# GPS.net
KiCad netlist of a schematic drawn in EAGLE
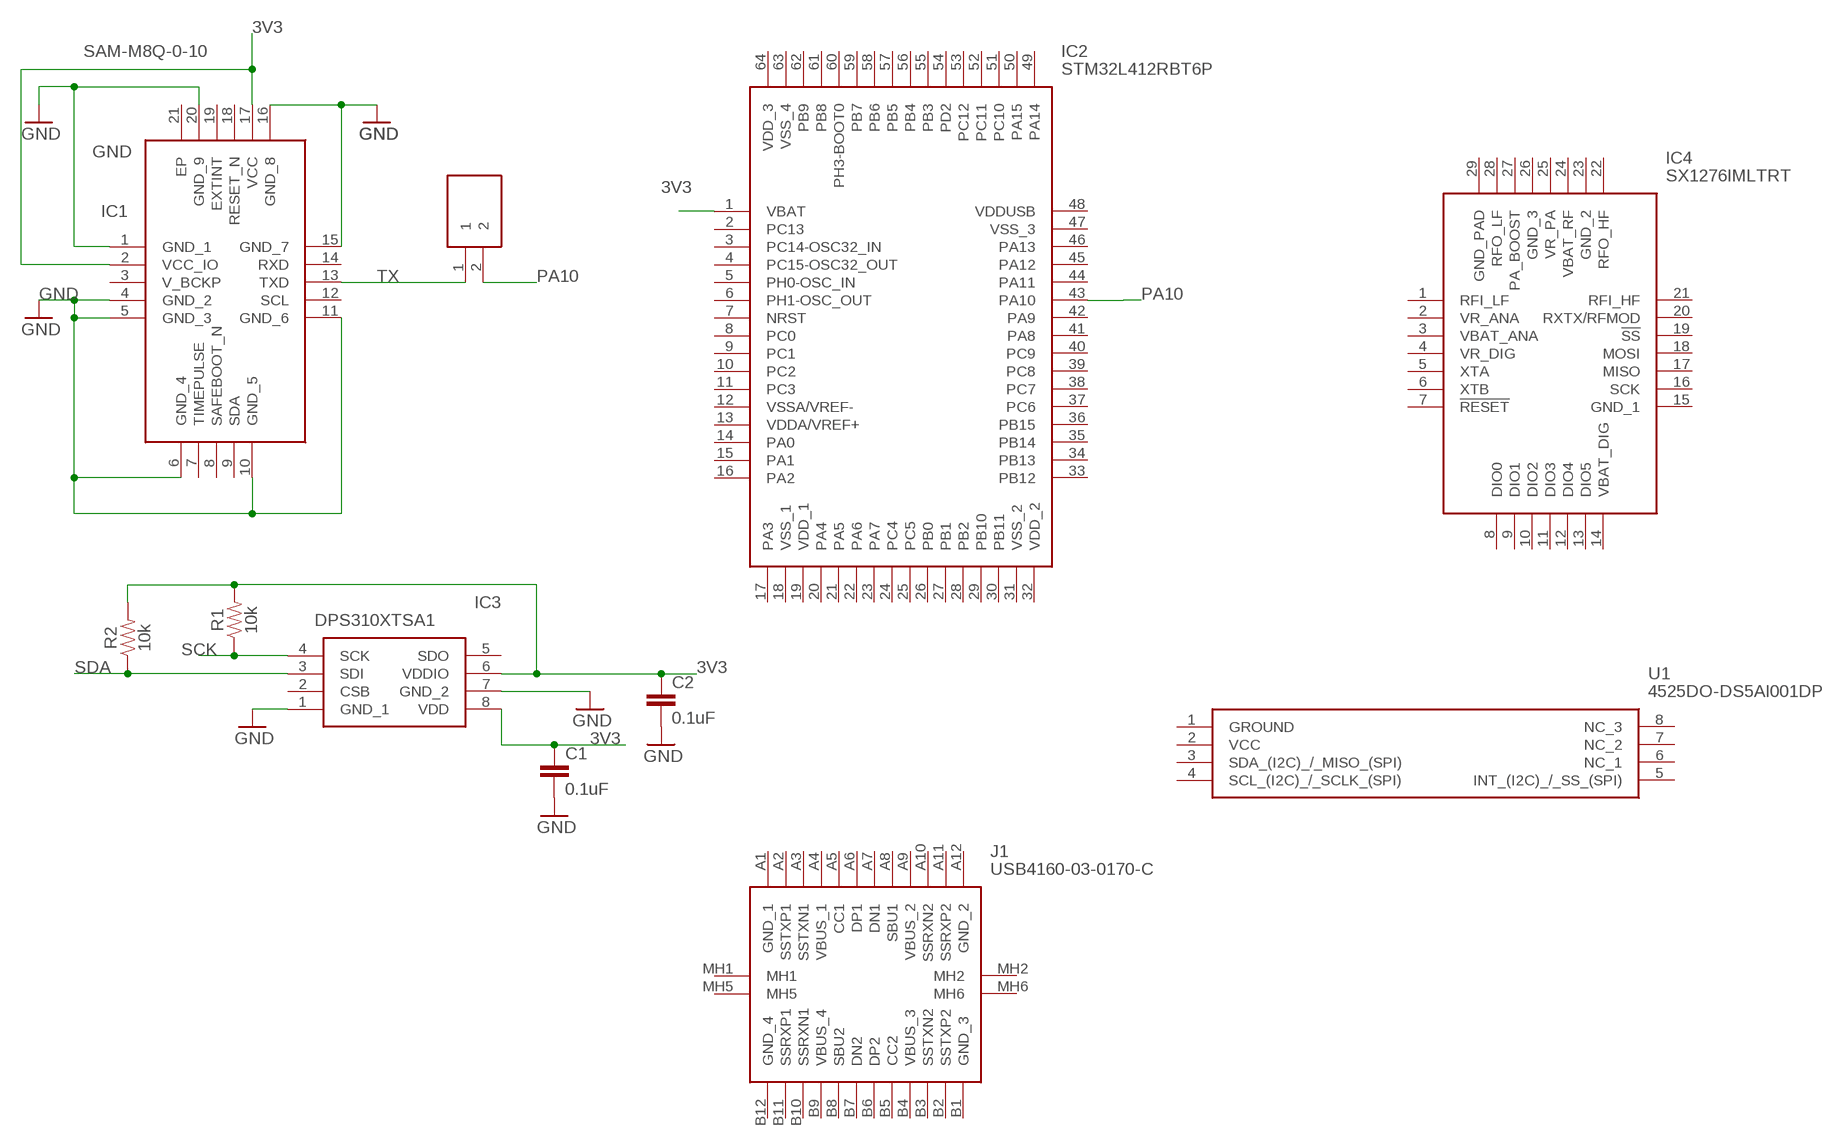
[diagram p0: schematic, sheet 1]

(export (version "E")
  (design (tool "Eeschema 10.0.6"))
  (components
    (comp (ref "C1")
      (value "0.1uF")
      (footprint "eagle-import:0402")
      (libsource (lib "eagle-import") (part "0.1UF-0402-6.3V-10%-X7R"))
    )
    (comp (ref "C2")
      (value "0.1uF")
      (footprint "eagle-import:0402")
      (libsource (lib "eagle-import") (part "0.1UF-0402-6.3V-10%-X7R"))
    )
    (comp (ref "FB1")
      (value "BLM15HD102SN1")
      (footprint "eagle-import:NFZ15SG152SN10B")
      (libsource (lib "eagle-import") (part "BLM15HD102SN1"))
    )
    (comp (ref "IC1")
      (value "SAM-M8Q-0-10")
      (footprint "eagle-import:SAMM8Q010")
      (libsource (lib "eagle-import") (part "SAM-M8Q-0-10"))
    )
    (comp (ref "IC2")
      (value "STM32L412RBT6P")
      (footprint "eagle-import:QFP50P1200X1200X160-64N")
      (fields (field (name "MOUSER_PART_NUMBER") "511-STM32L412RBT6P"))
      (libsource (lib "eagle-import") (part "STM32L412RBT6P"))
    )
    (comp (ref "IC3")
      (value "DPS310XTSA1")
      (footprint "eagle-import:DPS310XTSA1")
      (fields (field (name "MOUSER_PART_NUMBER") "726-DPS310XTSA1"))
      (libsource (lib "eagle-import") (part "DPS310XTSA1"))
    )
    (comp (ref "IC4")
      (value "SX1276IMLTRT")
      (footprint "eagle-import:QFN65P600X600X100-29N")
      (fields (field (name "MOUSER_PART_NUMBER") "947-SX1276IMLTRT"))
      (libsource (lib "eagle-import") (part "SX1276IMLTRT"))
    )
    (comp (ref "J1")
      (value "USB4160-03-0170-C")
      (footprint "eagle-import:USB4160030170C")
      (fields (field (name "MOUSER_PART_NUMBER") "640-USB4160-3-0170-C"))
      (libsource (lib "eagle-import") (part "USB4160-03-0170-C"))
    )
    (comp (ref "R1")
      (value "10k")
      (footprint "eagle-import:0402")
      (libsource (lib "eagle-import") (part "10KOHM-0402-1/16W-1%"))
    )
    (comp (ref "R2")
      (value "10k")
      (footprint "eagle-import:0402")
      (libsource (lib "eagle-import") (part "10KOHM-0402-1/16W-1%"))
    )
    (comp (ref "U1")
      (value "4525DO-DS5AI001DP")
      (footprint "eagle-import:4525DO-DS...P")
      (fields (field (name "MOUSER_PART_NUMBER") "824-4525DODS5AI001DP"))
      (libsource (lib "eagle-import") (part "4525DO-DS5AI001DP"))
    )
  )
  (nets
    (net (code "1") (name "/3V3") (class "Default")
      (node (ref "C1") (pin "1") (pinfunction "1_1") (pintype "passive"))
      (node (ref "C2") (pin "1") (pinfunction "1_1") (pintype "passive"))
      (node (ref "IC1") (pin "17") (pinfunction "VCC_17") (pintype "bidirectional"))
      (node (ref "IC1") (pin "2") (pinfunction "VCC_IO_2") (pintype "bidirectional"))
      (node (ref "IC2") (pin "1") (pinfunction "VBAT_1") (pintype "bidirectional"))
      (node (ref "IC3") (pin "6") (pinfunction "VDDIO_6") (pintype "bidirectional"))
      (node (ref "IC3") (pin "8") (pinfunction "VDD_8") (pintype "bidirectional"))
      (node (ref "R1") (pin "2") (pinfunction "2_2") (pintype "passive"))
      (node (ref "R2") (pin "2") (pinfunction "2_2") (pintype "passive"))
    )
    (net (code "2") (name "/GROUND") (class "Default")
      (node (ref "U1") (pin "1") (pinfunction "GROUND_1") (pintype "power_in"))
    )
    (net (code "3") (name "/PA10") (class "Default")
      (node (ref "FB1") (pin "2") (pinfunction "2_2") (pintype "bidirectional"))
      (node (ref "IC2") (pin "43") (pinfunction "PA10_43") (pintype "bidirectional"))
    )
    (net (code "4") (name "/SCK") (class "Default")
      (node (ref "IC3") (pin "4") (pinfunction "SCK_4") (pintype "bidirectional"))
      (node (ref "R1") (pin "1") (pinfunction "1_1") (pintype "passive"))
    )
    (net (code "5") (name "/SDA") (class "Default")
      (node (ref "IC3") (pin "3") (pinfunction "SDI_3") (pintype "bidirectional"))
      (node (ref "R2") (pin "1") (pinfunction "1_1") (pintype "passive"))
    )
    (net (code "6") (name "/TX") (class "Default")
      (node (ref "FB1") (pin "1") (pinfunction "1_1") (pintype "bidirectional"))
      (node (ref "IC1") (pin "13") (pinfunction "TXD_13") (pintype "bidirectional"))
    )
    (net (code "7") (name "/VCC") (class "Default")
      (node (ref "U1") (pin "2") (pinfunction "VCC_2") (pintype "power_in"))
    )
    (net (code "8") (name "GND") (class "Default")
      (node (ref "C1") (pin "2") (pinfunction "2_2") (pintype "passive"))
      (node (ref "C2") (pin "2") (pinfunction "2_2") (pintype "passive"))
      (node (ref "IC1") (pin "1") (pinfunction "GND_1_1") (pintype "bidirectional"))
      (node (ref "IC1") (pin "10") (pinfunction "GND_5_10") (pintype "bidirectional"))
      (node (ref "IC1") (pin "11") (pinfunction "GND_6_11") (pintype "bidirectional"))
      (node (ref "IC1") (pin "15") (pinfunction "GND_7_15") (pintype "bidirectional"))
      (node (ref "IC1") (pin "16") (pinfunction "GND_8_16") (pintype "bidirectional"))
      (node (ref "IC1") (pin "20") (pinfunction "GND_9_20") (pintype "bidirectional"))
      (node (ref "IC1") (pin "4") (pinfunction "GND_2_4") (pintype "bidirectional"))
      (node (ref "IC1") (pin "5") (pinfunction "GND_3_5") (pintype "bidirectional"))
      (node (ref "IC1") (pin "6") (pinfunction "GND_4_6") (pintype "bidirectional"))
      (node (ref "IC3") (pin "1") (pinfunction "GND_1_1") (pintype "bidirectional"))
      (node (ref "IC3") (pin "7") (pinfunction "GND_2_7") (pintype "bidirectional"))
    )
    (net (code "9") (name "unconnected-(IC1-EP-Pad21)") (class "Default")
      (node (ref "IC1") (pin "21") (pinfunction "EP_21") (pintype "bidirectional"))
    )
    (net (code "10") (name "unconnected-(IC1-EXTINT-Pad19)") (class "Default")
      (node (ref "IC1") (pin "19") (pinfunction "EXTINT_19") (pintype "bidirectional"))
    )
    (net (code "11") (name "unconnected-(IC1-RESET_N-Pad18)") (class "Default")
      (node (ref "IC1") (pin "18") (pinfunction "RESET_N_18") (pintype "bidirectional"))
    )
    (net (code "12") (name "unconnected-(IC1-RXD-Pad14)") (class "Default")
      (node (ref "IC1") (pin "14") (pinfunction "RXD_14") (pintype "bidirectional"))
    )
    (net (code "13") (name "unconnected-(IC1-SAFEBOOT_N-Pad8)") (class "Default")
      (node (ref "IC1") (pin "8") (pinfunction "SAFEBOOT_N_8") (pintype "bidirectional"))
    )
    (net (code "14") (name "unconnected-(IC1-SCL-Pad12)") (class "Default")
      (node (ref "IC1") (pin "12") (pinfunction "SCL_12") (pintype "bidirectional"))
    )
    (net (code "15") (name "unconnected-(IC1-SDA-Pad9)") (class "Default")
      (node (ref "IC1") (pin "9") (pinfunction "SDA_9") (pintype "bidirectional"))
    )
    (net (code "16") (name "unconnected-(IC1-TIMEPULSE-Pad7)") (class "Default")
      (node (ref "IC1") (pin "7") (pinfunction "TIMEPULSE_7") (pintype "bidirectional"))
    )
    (net (code "17") (name "unconnected-(IC1-V_BCKP-Pad3)") (class "Default")
      (node (ref "IC1") (pin "3") (pinfunction "V_BCKP_3") (pintype "bidirectional"))
    )
    (net (code "18") (name "unconnected-(IC2-NRST-Pad7)") (class "Default")
      (node (ref "IC2") (pin "7") (pinfunction "NRST_7") (pintype "bidirectional"))
    )
    (net (code "19") (name "unconnected-(IC2-PA0-Pad14)") (class "Default")
      (node (ref "IC2") (pin "14") (pinfunction "PA0_14") (pintype "bidirectional"))
    )
    (net (code "20") (name "unconnected-(IC2-PA1-Pad15)") (class "Default")
      (node (ref "IC2") (pin "15") (pinfunction "PA1_15") (pintype "bidirectional"))
    )
    (net (code "21") (name "unconnected-(IC2-PA2-Pad16)") (class "Default")
      (node (ref "IC2") (pin "16") (pinfunction "PA2_16") (pintype "bidirectional"))
    )
    (net (code "22") (name "unconnected-(IC2-PA3-Pad17)") (class "Default")
      (node (ref "IC2") (pin "17") (pinfunction "PA3_17") (pintype "bidirectional"))
    )
    (net (code "23") (name "unconnected-(IC2-PA4-Pad20)") (class "Default")
      (node (ref "IC2") (pin "20") (pinfunction "PA4_20") (pintype "bidirectional"))
    )
    (net (code "24") (name "unconnected-(IC2-PA5-Pad21)") (class "Default")
      (node (ref "IC2") (pin "21") (pinfunction "PA5_21") (pintype "bidirectional"))
    )
    (net (code "25") (name "unconnected-(IC2-PA6-Pad22)") (class "Default")
      (node (ref "IC2") (pin "22") (pinfunction "PA6_22") (pintype "bidirectional"))
    )
    (net (code "26") (name "unconnected-(IC2-PA7-Pad23)") (class "Default")
      (node (ref "IC2") (pin "23") (pinfunction "PA7_23") (pintype "bidirectional"))
    )
    (net (code "27") (name "unconnected-(IC2-PA8-Pad41)") (class "Default")
      (node (ref "IC2") (pin "41") (pinfunction "PA8_41") (pintype "bidirectional"))
    )
    (net (code "28") (name "unconnected-(IC2-PA9-Pad42)") (class "Default")
      (node (ref "IC2") (pin "42") (pinfunction "PA9_42") (pintype "bidirectional"))
    )
    (net (code "29") (name "unconnected-(IC2-PA11-Pad44)") (class "Default")
      (node (ref "IC2") (pin "44") (pinfunction "PA11_44") (pintype "bidirectional"))
    )
    (net (code "30") (name "unconnected-(IC2-PA12-Pad45)") (class "Default")
      (node (ref "IC2") (pin "45") (pinfunction "PA12_45") (pintype "bidirectional"))
    )
    (net (code "31") (name "unconnected-(IC2-PA13-Pad46)") (class "Default")
      (node (ref "IC2") (pin "46") (pinfunction "PA13_46") (pintype "bidirectional"))
    )
    (net (code "32") (name "unconnected-(IC2-PA14-Pad49)") (class "Default")
      (node (ref "IC2") (pin "49") (pinfunction "PA14_49") (pintype "bidirectional"))
    )
    (net (code "33") (name "unconnected-(IC2-PA15-Pad50)") (class "Default")
      (node (ref "IC2") (pin "50") (pinfunction "PA15_50") (pintype "bidirectional"))
    )
    (net (code "34") (name "unconnected-(IC2-PB0-Pad26)") (class "Default")
      (node (ref "IC2") (pin "26") (pinfunction "PB0_26") (pintype "bidirectional"))
    )
    (net (code "35") (name "unconnected-(IC2-PB1-Pad27)") (class "Default")
      (node (ref "IC2") (pin "27") (pinfunction "PB1_27") (pintype "bidirectional"))
    )
    (net (code "36") (name "unconnected-(IC2-PB2-Pad28)") (class "Default")
      (node (ref "IC2") (pin "28") (pinfunction "PB2_28") (pintype "bidirectional"))
    )
    (net (code "37") (name "unconnected-(IC2-PB3-Pad55)") (class "Default")
      (node (ref "IC2") (pin "55") (pinfunction "PB3_55") (pintype "bidirectional"))
    )
    (net (code "38") (name "unconnected-(IC2-PB4-Pad56)") (class "Default")
      (node (ref "IC2") (pin "56") (pinfunction "PB4_56") (pintype "bidirectional"))
    )
    (net (code "39") (name "unconnected-(IC2-PB5-Pad57)") (class "Default")
      (node (ref "IC2") (pin "57") (pinfunction "PB5_57") (pintype "bidirectional"))
    )
    (net (code "40") (name "unconnected-(IC2-PB6-Pad58)") (class "Default")
      (node (ref "IC2") (pin "58") (pinfunction "PB6_58") (pintype "bidirectional"))
    )
    (net (code "41") (name "unconnected-(IC2-PB7-Pad59)") (class "Default")
      (node (ref "IC2") (pin "59") (pinfunction "PB7_59") (pintype "bidirectional"))
    )
    (net (code "42") (name "unconnected-(IC2-PB8-Pad61)") (class "Default")
      (node (ref "IC2") (pin "61") (pinfunction "PB8_61") (pintype "bidirectional"))
    )
    (net (code "43") (name "unconnected-(IC2-PB9-Pad62)") (class "Default")
      (node (ref "IC2") (pin "62") (pinfunction "PB9_62") (pintype "bidirectional"))
    )
    (net (code "44") (name "unconnected-(IC2-PB10-Pad29)") (class "Default")
      (node (ref "IC2") (pin "29") (pinfunction "PB10_29") (pintype "bidirectional"))
    )
    (net (code "45") (name "unconnected-(IC2-PB11-Pad30)") (class "Default")
      (node (ref "IC2") (pin "30") (pinfunction "PB11_30") (pintype "bidirectional"))
    )
    (net (code "46") (name "unconnected-(IC2-PB12-Pad33)") (class "Default")
      (node (ref "IC2") (pin "33") (pinfunction "PB12_33") (pintype "bidirectional"))
    )
    (net (code "47") (name "unconnected-(IC2-PB13-Pad34)") (class "Default")
      (node (ref "IC2") (pin "34") (pinfunction "PB13_34") (pintype "bidirectional"))
    )
    (net (code "48") (name "unconnected-(IC2-PB14-Pad35)") (class "Default")
      (node (ref "IC2") (pin "35") (pinfunction "PB14_35") (pintype "bidirectional"))
    )
    (net (code "49") (name "unconnected-(IC2-PB15-Pad36)") (class "Default")
      (node (ref "IC2") (pin "36") (pinfunction "PB15_36") (pintype "bidirectional"))
    )
    (net (code "50") (name "unconnected-(IC2-PC0-Pad8)") (class "Default")
      (node (ref "IC2") (pin "8") (pinfunction "PC0_8") (pintype "bidirectional"))
    )
    (net (code "51") (name "unconnected-(IC2-PC1-Pad9)") (class "Default")
      (node (ref "IC2") (pin "9") (pinfunction "PC1_9") (pintype "bidirectional"))
    )
    (net (code "52") (name "unconnected-(IC2-PC2-Pad10)") (class "Default")
      (node (ref "IC2") (pin "10") (pinfunction "PC2_10") (pintype "bidirectional"))
    )
    (net (code "53") (name "unconnected-(IC2-PC3-Pad11)") (class "Default")
      (node (ref "IC2") (pin "11") (pinfunction "PC3_11") (pintype "bidirectional"))
    )
    (net (code "54") (name "unconnected-(IC2-PC4-Pad24)") (class "Default")
      (node (ref "IC2") (pin "24") (pinfunction "PC4_24") (pintype "bidirectional"))
    )
    (net (code "55") (name "unconnected-(IC2-PC5-Pad25)") (class "Default")
      (node (ref "IC2") (pin "25") (pinfunction "PC5_25") (pintype "bidirectional"))
    )
    (net (code "56") (name "unconnected-(IC2-PC6-Pad37)") (class "Default")
      (node (ref "IC2") (pin "37") (pinfunction "PC6_37") (pintype "bidirectional"))
    )
    (net (code "57") (name "unconnected-(IC2-PC7-Pad38)") (class "Default")
      (node (ref "IC2") (pin "38") (pinfunction "PC7_38") (pintype "bidirectional"))
    )
    (net (code "58") (name "unconnected-(IC2-PC8-Pad39)") (class "Default")
      (node (ref "IC2") (pin "39") (pinfunction "PC8_39") (pintype "bidirectional"))
    )
    (net (code "59") (name "unconnected-(IC2-PC9-Pad40)") (class "Default")
      (node (ref "IC2") (pin "40") (pinfunction "PC9_40") (pintype "bidirectional"))
    )
    (net (code "60") (name "unconnected-(IC2-PC10-Pad51)") (class "Default")
      (node (ref "IC2") (pin "51") (pinfunction "PC10_51") (pintype "bidirectional"))
    )
    (net (code "61") (name "unconnected-(IC2-PC11-Pad52)") (class "Default")
      (node (ref "IC2") (pin "52") (pinfunction "PC11_52") (pintype "bidirectional"))
    )
    (net (code "62") (name "unconnected-(IC2-PC12-Pad53)") (class "Default")
      (node (ref "IC2") (pin "53") (pinfunction "PC12_53") (pintype "bidirectional"))
    )
    (net (code "63") (name "unconnected-(IC2-PC13-Pad2)") (class "Default")
      (node (ref "IC2") (pin "2") (pinfunction "PC13_2") (pintype "bidirectional"))
    )
    (net (code "64") (name "unconnected-(IC2-PC14-OSC32_IN-Pad3)") (class "Default")
      (node (ref "IC2") (pin "3") (pinfunction "PC14-OSC32_IN_3") (pintype "bidirectional"))
    )
    (net (code "65") (name "unconnected-(IC2-PC15-OSC32_OUT-Pad4)") (class "Default")
      (node (ref "IC2") (pin "4") (pinfunction "PC15-OSC32_OUT_4") (pintype "bidirectional"))
    )
    (net (code "66") (name "unconnected-(IC2-PD2-Pad54)") (class "Default")
      (node (ref "IC2") (pin "54") (pinfunction "PD2_54") (pintype "bidirectional"))
    )
    (net (code "67") (name "unconnected-(IC2-PH0-OSC_IN-Pad5)") (class "Default")
      (node (ref "IC2") (pin "5") (pinfunction "PH0-OSC_IN_5") (pintype "bidirectional"))
    )
    (net (code "68") (name "unconnected-(IC2-PH1-OSC_OUT-Pad6)") (class "Default")
      (node (ref "IC2") (pin "6") (pinfunction "PH1-OSC_OUT_6") (pintype "bidirectional"))
    )
    (net (code "69") (name "unconnected-(IC2-PH3-BOOT0-Pad60)") (class "Default")
      (node (ref "IC2") (pin "60") (pinfunction "PH3-BOOT0_60") (pintype "bidirectional"))
    )
    (net (code "70") (name "unconnected-(IC2-VDDA{slash}VREF+-Pad13)") (class "Default")
      (node (ref "IC2") (pin "13") (pinfunction "VDDA/VREF+_13") (pintype "bidirectional"))
    )
    (net (code "71") (name "unconnected-(IC2-VDDUSB-Pad48)") (class "Default")
      (node (ref "IC2") (pin "48") (pinfunction "VDDUSB_48") (pintype "bidirectional"))
    )
    (net (code "72") (name "unconnected-(IC2-VDD_1-Pad19)") (class "Default")
      (node (ref "IC2") (pin "19") (pinfunction "VDD_1_19") (pintype "bidirectional"))
    )
    (net (code "73") (name "unconnected-(IC2-VDD_2-Pad32)") (class "Default")
      (node (ref "IC2") (pin "32") (pinfunction "VDD_2_32") (pintype "bidirectional"))
    )
    (net (code "74") (name "unconnected-(IC2-VDD_3-Pad64)") (class "Default")
      (node (ref "IC2") (pin "64") (pinfunction "VDD_3_64") (pintype "bidirectional"))
    )
    (net (code "75") (name "unconnected-(IC2-VSSA{slash}VREF--Pad12)") (class "Default")
      (node (ref "IC2") (pin "12") (pinfunction "VSSA/VREF-_12") (pintype "bidirectional"))
    )
    (net (code "76") (name "unconnected-(IC2-VSS_1-Pad18)") (class "Default")
      (node (ref "IC2") (pin "18") (pinfunction "VSS_1_18") (pintype "bidirectional"))
    )
    (net (code "77") (name "unconnected-(IC2-VSS_2-Pad31)") (class "Default")
      (node (ref "IC2") (pin "31") (pinfunction "VSS_2_31") (pintype "bidirectional"))
    )
    (net (code "78") (name "unconnected-(IC2-VSS_3-Pad47)") (class "Default")
      (node (ref "IC2") (pin "47") (pinfunction "VSS_3_47") (pintype "bidirectional"))
    )
    (net (code "79") (name "unconnected-(IC2-VSS_4-Pad63)") (class "Default")
      (node (ref "IC2") (pin "63") (pinfunction "VSS_4_63") (pintype "bidirectional"))
    )
    (net (code "80") (name "unconnected-(IC3-CSB-Pad2)") (class "Default")
      (node (ref "IC3") (pin "2") (pinfunction "CSB_2") (pintype "bidirectional"))
    )
    (net (code "81") (name "unconnected-(IC3-SDO-Pad5)") (class "Default")
      (node (ref "IC3") (pin "5") (pinfunction "SDO_5") (pintype "bidirectional"))
    )
    (net (code "82") (name "unconnected-(IC4-DIO0-Pad8)") (class "Default")
      (node (ref "IC4") (pin "8") (pinfunction "DIO0_8") (pintype "bidirectional"))
    )
    (net (code "83") (name "unconnected-(IC4-DIO1-Pad9)") (class "Default")
      (node (ref "IC4") (pin "9") (pinfunction "DIO1_9") (pintype "bidirectional"))
    )
    (net (code "84") (name "unconnected-(IC4-DIO2-Pad10)") (class "Default")
      (node (ref "IC4") (pin "10") (pinfunction "DIO2_10") (pintype "bidirectional"))
    )
    (net (code "85") (name "unconnected-(IC4-DIO3-Pad11)") (class "Default")
      (node (ref "IC4") (pin "11") (pinfunction "DIO3_11") (pintype "bidirectional"))
    )
    (net (code "86") (name "unconnected-(IC4-DIO4-Pad12)") (class "Default")
      (node (ref "IC4") (pin "12") (pinfunction "DIO4_12") (pintype "bidirectional"))
    )
    (net (code "87") (name "unconnected-(IC4-DIO5-Pad13)") (class "Default")
      (node (ref "IC4") (pin "13") (pinfunction "DIO5_13") (pintype "bidirectional"))
    )
    (net (code "88") (name "unconnected-(IC4-GND_1-Pad15)") (class "Default")
      (node (ref "IC4") (pin "15") (pinfunction "GND_1_15") (pintype "bidirectional"))
    )
    (net (code "89") (name "unconnected-(IC4-GND_2-Pad23)") (class "Default")
      (node (ref "IC4") (pin "23") (pinfunction "GND_2_23") (pintype "bidirectional"))
    )
    (net (code "90") (name "unconnected-(IC4-GND_3-Pad26)") (class "Default")
      (node (ref "IC4") (pin "26") (pinfunction "GND_3_26") (pintype "bidirectional"))
    )
    (net (code "91") (name "unconnected-(IC4-GND_PAD-Pad29)") (class "Default")
      (node (ref "IC4") (pin "29") (pinfunction "GND_PAD_29") (pintype "bidirectional"))
    )
    (net (code "92") (name "unconnected-(IC4-MISO-Pad17)") (class "Default")
      (node (ref "IC4") (pin "17") (pinfunction "MISO_17") (pintype "bidirectional"))
    )
    (net (code "93") (name "unconnected-(IC4-MOSI-Pad18)") (class "Default")
      (node (ref "IC4") (pin "18") (pinfunction "MOSI_18") (pintype "bidirectional"))
    )
    (net (code "94") (name "unconnected-(IC4-PA_BOOST-Pad27)") (class "Default")
      (node (ref "IC4") (pin "27") (pinfunction "PA_BOOST_27") (pintype "bidirectional"))
    )
    (net (code "95") (name "unconnected-(IC4-RFI_HF-Pad21)") (class "Default")
      (node (ref "IC4") (pin "21") (pinfunction "RFI_HF_21") (pintype "bidirectional"))
    )
    (net (code "96") (name "unconnected-(IC4-RFI_LF-Pad1)") (class "Default")
      (node (ref "IC4") (pin "1") (pinfunction "RFI_LF_1") (pintype "bidirectional"))
    )
    (net (code "97") (name "unconnected-(IC4-RFO_HF-Pad22)") (class "Default")
      (node (ref "IC4") (pin "22") (pinfunction "RFO_HF_22") (pintype "bidirectional"))
    )
    (net (code "98") (name "unconnected-(IC4-RFO_LF-Pad28)") (class "Default")
      (node (ref "IC4") (pin "28") (pinfunction "RFO_LF_28") (pintype "bidirectional"))
    )
    (net (code "99") (name "unconnected-(IC4-RXTX{slash}RFMOD-Pad20)") (class "Default")
      (node (ref "IC4") (pin "20") (pinfunction "RXTX/RFMOD_20") (pintype "bidirectional"))
    )
    (net (code "100") (name "unconnected-(IC4-SCK-Pad16)") (class "Default")
      (node (ref "IC4") (pin "16") (pinfunction "SCK_16") (pintype "bidirectional"))
    )
    (net (code "101") (name "unconnected-(IC4-VBAT_ANA-Pad3)") (class "Default")
      (node (ref "IC4") (pin "3") (pinfunction "VBAT_ANA_3") (pintype "bidirectional"))
    )
    (net (code "102") (name "unconnected-(IC4-VBAT_DIG-Pad14)") (class "Default")
      (node (ref "IC4") (pin "14") (pinfunction "VBAT_DIG_14") (pintype "bidirectional"))
    )
    (net (code "103") (name "unconnected-(IC4-VBAT_RF-Pad24)") (class "Default")
      (node (ref "IC4") (pin "24") (pinfunction "VBAT_RF_24") (pintype "bidirectional"))
    )
    (net (code "104") (name "unconnected-(IC4-VR_ANA-Pad2)") (class "Default")
      (node (ref "IC4") (pin "2") (pinfunction "VR_ANA_2") (pintype "bidirectional"))
    )
    (net (code "105") (name "unconnected-(IC4-VR_DIG-Pad4)") (class "Default")
      (node (ref "IC4") (pin "4") (pinfunction "VR_DIG_4") (pintype "bidirectional"))
    )
    (net (code "106") (name "unconnected-(IC4-VR_PA-Pad25)") (class "Default")
      (node (ref "IC4") (pin "25") (pinfunction "VR_PA_25") (pintype "bidirectional"))
    )
    (net (code "107") (name "unconnected-(IC4-XTA-Pad5)") (class "Default")
      (node (ref "IC4") (pin "5") (pinfunction "XTA_5") (pintype "bidirectional"))
    )
    (net (code "108") (name "unconnected-(IC4-XTB-Pad6)") (class "Default")
      (node (ref "IC4") (pin "6") (pinfunction "XTB_6") (pintype "bidirectional"))
    )
    (net (code "109") (name "unconnected-(IC4-~{RESET}-Pad7)") (class "Default")
      (node (ref "IC4") (pin "7") (pinfunction "~{RESET}_7") (pintype "bidirectional"))
    )
    (net (code "110") (name "unconnected-(IC4-~{SS}-Pad19)") (class "Default")
      (node (ref "IC4") (pin "19") (pinfunction "~{SS}_19") (pintype "bidirectional"))
    )
    (net (code "111") (name "unconnected-(J1-CC1-PadA5)") (class "Default")
      (node (ref "J1") (pin "A5") (pinfunction "CC1_A5") (pintype "bidirectional"))
    )
    (net (code "112") (name "unconnected-(J1-CC2-PadB5)") (class "Default")
      (node (ref "J1") (pin "B5") (pinfunction "CC2_B5") (pintype "bidirectional"))
    )
    (net (code "113") (name "unconnected-(J1-DN1-PadA7)") (class "Default")
      (node (ref "J1") (pin "A7") (pinfunction "DN1_A7") (pintype "bidirectional"))
    )
    (net (code "114") (name "unconnected-(J1-DN2-PadB7)") (class "Default")
      (node (ref "J1") (pin "B7") (pinfunction "DN2_B7") (pintype "bidirectional"))
    )
    (net (code "115") (name "unconnected-(J1-DP1-PadA6)") (class "Default")
      (node (ref "J1") (pin "A6") (pinfunction "DP1_A6") (pintype "bidirectional"))
    )
    (net (code "116") (name "unconnected-(J1-DP2-PadB6)") (class "Default")
      (node (ref "J1") (pin "B6") (pinfunction "DP2_B6") (pintype "bidirectional"))
    )
    (net (code "117") (name "unconnected-(J1-GND_1-PadA1)") (class "Default")
      (node (ref "J1") (pin "A1") (pinfunction "GND_1_A1") (pintype "bidirectional"))
    )
    (net (code "118") (name "unconnected-(J1-GND_2-PadA12)") (class "Default")
      (node (ref "J1") (pin "A12") (pinfunction "GND_2_A12") (pintype "bidirectional"))
    )
    (net (code "119") (name "unconnected-(J1-GND_3-PadB1)") (class "Default")
      (node (ref "J1") (pin "B1") (pinfunction "GND_3_B1") (pintype "bidirectional"))
    )
    (net (code "120") (name "unconnected-(J1-GND_4-PadB12)") (class "Default")
      (node (ref "J1") (pin "B12") (pinfunction "GND_4_B12") (pintype "bidirectional"))
    )
    (net (code "121") (name "unconnected-(J1-PadMH1)") (class "Default")
      (node (ref "J1") (pin "MH1") (pinfunction "MH1_MH1") (pintype "bidirectional"))
    )
    (net (code "122") (name "unconnected-(J1-PadMH2)") (class "Default")
      (node (ref "J1") (pin "MH2") (pinfunction "MH2_MH2") (pintype "bidirectional"))
    )
    (net (code "123") (name "unconnected-(J1-PadMH5)") (class "Default")
      (node (ref "J1") (pin "MH5") (pinfunction "MH5_MH5") (pintype "bidirectional"))
    )
    (net (code "124") (name "unconnected-(J1-PadMH6)") (class "Default")
      (node (ref "J1") (pin "MH6") (pinfunction "MH6_MH6") (pintype "bidirectional"))
    )
    (net (code "125") (name "unconnected-(J1-SBU1-PadA8)") (class "Default")
      (node (ref "J1") (pin "A8") (pinfunction "SBU1_A8") (pintype "bidirectional"))
    )
    (net (code "126") (name "unconnected-(J1-SBU2-PadB8)") (class "Default")
      (node (ref "J1") (pin "B8") (pinfunction "SBU2_B8") (pintype "bidirectional"))
    )
    (net (code "127") (name "unconnected-(J1-SSRXN1-PadB10)") (class "Default")
      (node (ref "J1") (pin "B10") (pinfunction "SSRXN1_B10") (pintype "bidirectional"))
    )
    (net (code "128") (name "unconnected-(J1-SSRXN2-PadA10)") (class "Default")
      (node (ref "J1") (pin "A10") (pinfunction "SSRXN2_A10") (pintype "bidirectional"))
    )
    (net (code "129") (name "unconnected-(J1-SSRXP1-PadB11)") (class "Default")
      (node (ref "J1") (pin "B11") (pinfunction "SSRXP1_B11") (pintype "bidirectional"))
    )
    (net (code "130") (name "unconnected-(J1-SSRXP2-PadA11)") (class "Default")
      (node (ref "J1") (pin "A11") (pinfunction "SSRXP2_A11") (pintype "bidirectional"))
    )
    (net (code "131") (name "unconnected-(J1-SSTXN1-PadA3)") (class "Default")
      (node (ref "J1") (pin "A3") (pinfunction "SSTXN1_A3") (pintype "bidirectional"))
    )
    (net (code "132") (name "unconnected-(J1-SSTXN2-PadB3)") (class "Default")
      (node (ref "J1") (pin "B3") (pinfunction "SSTXN2_B3") (pintype "bidirectional"))
    )
    (net (code "133") (name "unconnected-(J1-SSTXP1-PadA2)") (class "Default")
      (node (ref "J1") (pin "A2") (pinfunction "SSTXP1_A2") (pintype "bidirectional"))
    )
    (net (code "134") (name "unconnected-(J1-SSTXP2-PadB2)") (class "Default")
      (node (ref "J1") (pin "B2") (pinfunction "SSTXP2_B2") (pintype "bidirectional"))
    )
    (net (code "135") (name "unconnected-(J1-VBUS_1-PadA4)") (class "Default")
      (node (ref "J1") (pin "A4") (pinfunction "VBUS_1_A4") (pintype "bidirectional"))
    )
    (net (code "136") (name "unconnected-(J1-VBUS_2-PadA9)") (class "Default")
      (node (ref "J1") (pin "A9") (pinfunction "VBUS_2_A9") (pintype "bidirectional"))
    )
    (net (code "137") (name "unconnected-(J1-VBUS_3-PadB4)") (class "Default")
      (node (ref "J1") (pin "B4") (pinfunction "VBUS_3_B4") (pintype "bidirectional"))
    )
    (net (code "138") (name "unconnected-(J1-VBUS_4-PadB9)") (class "Default")
      (node (ref "J1") (pin "B9") (pinfunction "VBUS_4_B9") (pintype "bidirectional"))
    )
    (net (code "139") (name "unconnected-(U1-INT_(I2C)_{slash}_SS_(SPI)-Pad5)") (class "Default")
      (node (ref "U1") (pin "5") (pinfunction "INT_(I2C)_/_SS_(SPI)_5") (pintype "bidirectional"))
    )
    (net (code "140") (name "unconnected-(U1-NC_1-Pad6)") (class "Default")
      (node (ref "U1") (pin "6") (pinfunction "NC_1_6") (pintype "bidirectional"))
    )
    (net (code "141") (name "unconnected-(U1-NC_2-Pad7)") (class "Default")
      (node (ref "U1") (pin "7") (pinfunction "NC_2_7") (pintype "bidirectional"))
    )
    (net (code "142") (name "unconnected-(U1-NC_3-Pad8)") (class "Default")
      (node (ref "U1") (pin "8") (pinfunction "NC_3_8") (pintype "bidirectional"))
    )
    (net (code "143") (name "unconnected-(U1-SCL_(I2C)_{slash}_SCLK_(SPI)-Pad4)") (class "Default")
      (node (ref "U1") (pin "4") (pinfunction "SCL_(I2C)_/_SCLK_(SPI)_4") (pintype "bidirectional"))
    )
    (net (code "144") (name "unconnected-(U1-SDA_(I2C)_{slash}_MISO_(SPI)-Pad3)") (class "Default")
      (node (ref "U1") (pin "3") (pinfunction "SDA_(I2C)_/_MISO_(SPI)_3") (pintype "bidirectional"))
    )
  )
)
